# main.net
KiCad netlist of a schematic drawn in Altium Designer
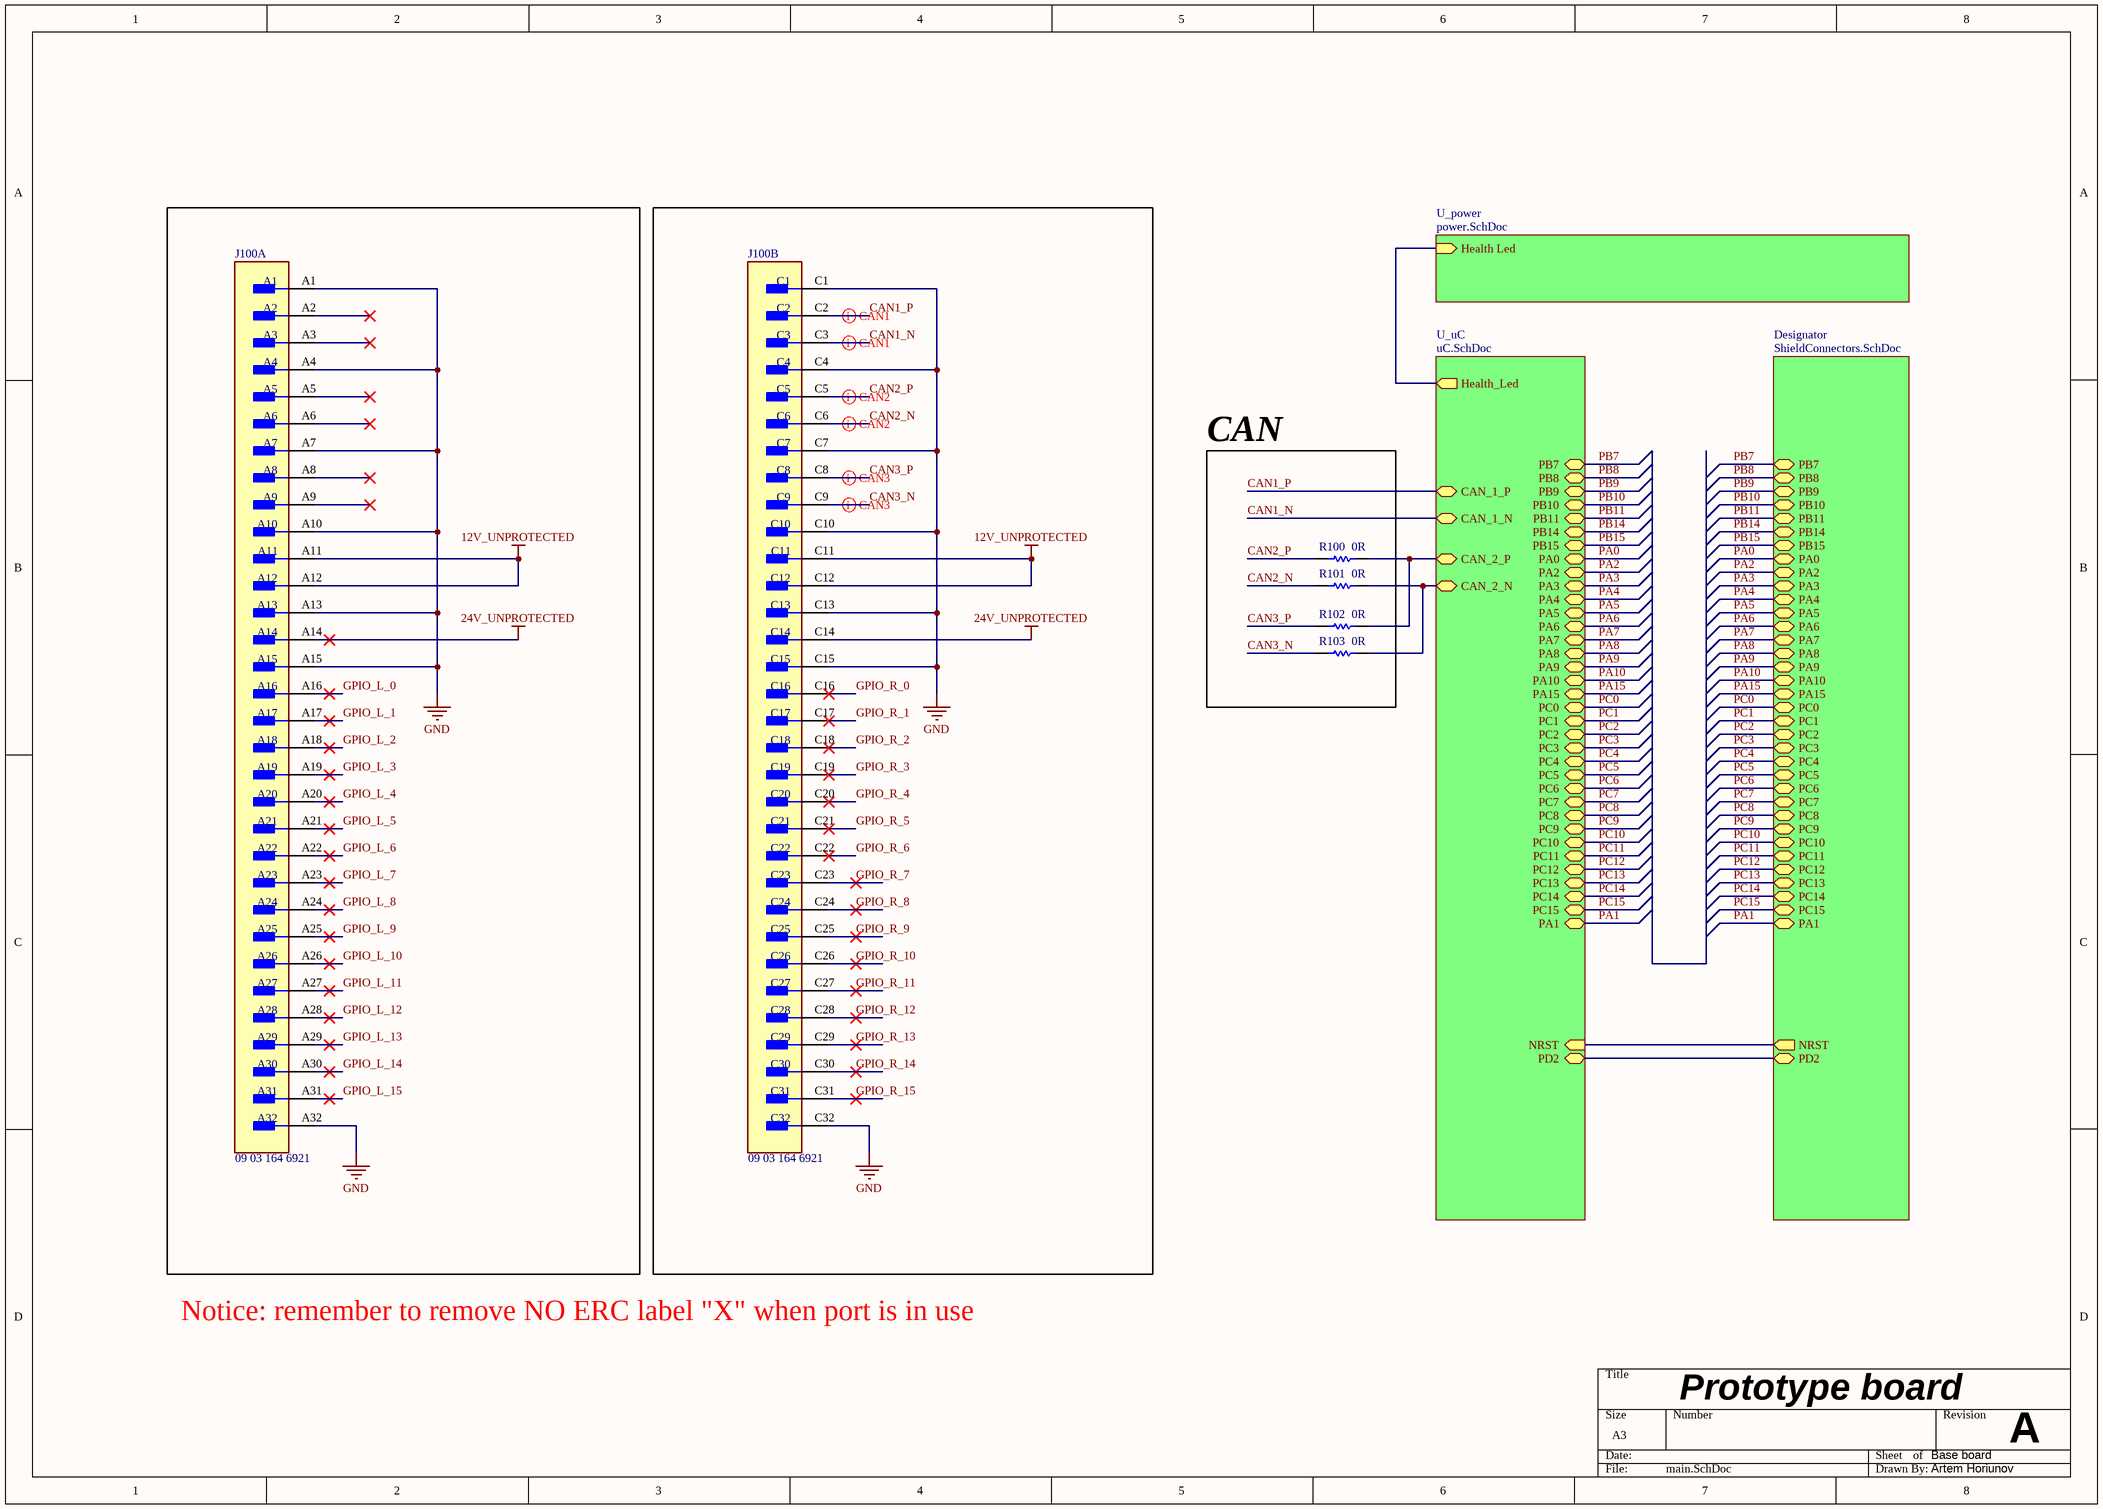
[diagram p0: main.SchDoc]

(export (version "E")
  (design (tool "Eeschema 10.0.6"))
  (components
    (comp (ref "J100")
      (value "09 03 164 6921")
      (footprint "FP-09_03_164_6921-MFG")
      (description "CONN DIN HDR 96POS PCB RA")
      (fields
        (field (name "MANUFACTURER") "Harting")
        (field (name "OCTOPART") "https://octopart.com/09031646921-harting+elektronik-42933")
      )
      (libsource (lib "Altium Content Vault") (part "242112e785ae82ea23b0e3c1eadb5b2"))
    )
    (comp (ref "R100")
      (value "0R")
      (footprint "RESC1608X55X25ML10T15")
      (description "Chip Resistor, 0 Ohm, +/- 5%, 0.1 W, -55 to 155 degC, 0603 (1608 Metric), RoHS, Tape and Reel")
      (fields (field (name "TOLERANCE") "5%") (field (name "MANUFACTURER") "Yageo"))
      (libsource (lib "Altium Content Vault") (part "RES-2"))
    )
    (comp (ref "R101")
      (value "0R")
      (footprint "RESC1608X55X25ML10T15")
      (description "Chip Resistor, 0 Ohm, +/- 5%, 0.1 W, -55 to 155 degC, 0603 (1608 Metric), RoHS, Tape and Reel")
      (fields (field (name "TOLERANCE") "5%") (field (name "MANUFACTURER") "Yageo"))
      (libsource (lib "Altium Content Vault") (part "RES-2"))
    )
    (comp (ref "R102")
      (value "0R")
      (footprint "RESC1608X55X25ML10T15")
      (description "Chip Resistor, 0 Ohm, +/- 5%, 0.1 W, -55 to 155 degC, 0603 (1608 Metric), RoHS, Tape and Reel")
      (fields (field (name "TOLERANCE") "5%") (field (name "MANUFACTURER") "Yageo"))
      (libsource (lib "Altium Content Vault") (part "RES-2"))
    )
    (comp (ref "R103")
      (value "0R")
      (footprint "RESC1608X55X25ML10T15")
      (description "Chip Resistor, 0 Ohm, +/- 5%, 0.1 W, -55 to 155 degC, 0603 (1608 Metric), RoHS, Tape and Reel")
      (fields (field (name "TOLERANCE") "5%") (field (name "MANUFACTURER") "Yageo"))
      (libsource (lib "Altium Content Vault") (part "RES-2"))
    )
  )
  (nets
    (net (code "1") (name "/CAN1_N") (class "Default")
      (node (ref "J100") (pin "C3") (pinfunction "C3_C3") (pintype "passive"))
    )
    (net (code "2") (name "/CAN1_P") (class "Default")
      (node (ref "J100") (pin "C2") (pinfunction "C2_C2") (pintype "passive"))
    )
    (net (code "3") (name "/CAN2_N") (class "Default")
      (node (ref "J100") (pin "C6") (pinfunction "C6_C6") (pintype "passive"))
      (node (ref "R101") (pin "1") (pinfunction "1_1") (pintype "passive"))
    )
    (net (code "4") (name "/CAN2_P") (class "Default")
      (node (ref "J100") (pin "C5") (pinfunction "C5_C5") (pintype "passive"))
      (node (ref "R100") (pin "1") (pinfunction "1_1") (pintype "passive"))
    )
    (net (code "5") (name "/CAN3_N") (class "Default")
      (node (ref "J100") (pin "C9") (pinfunction "C9_C9") (pintype "passive"))
      (node (ref "R103") (pin "1") (pinfunction "1_1") (pintype "passive"))
    )
    (net (code "6") (name "/CAN3_P") (class "Default")
      (node (ref "J100") (pin "C8") (pinfunction "C8_C8") (pintype "passive"))
      (node (ref "R102") (pin "1") (pinfunction "1_1") (pintype "passive"))
    )
    (net (code "7") (name "/CAN_2_N") (class "Default")
      (node (ref "R101") (pin "2") (pinfunction "2_2") (pintype "passive"))
      (node (ref "R103") (pin "2") (pinfunction "2_2") (pintype "passive"))
    )
    (net (code "8") (name "/CAN_2_P") (class "Default")
      (node (ref "R100") (pin "2") (pinfunction "2_2") (pintype "passive"))
      (node (ref "R102") (pin "2") (pinfunction "2_2") (pintype "passive"))
    )
    (net (code "9") (name "/GPIO_L_0") (class "Default")
      (node (ref "J100") (pin "A16") (pinfunction "A16_A16") (pintype "passive"))
    )
    (net (code "10") (name "/GPIO_L_1") (class "Default")
      (node (ref "J100") (pin "A17") (pinfunction "A17_A17") (pintype "passive"))
    )
    (net (code "11") (name "/GPIO_L_2") (class "Default")
      (node (ref "J100") (pin "A18") (pinfunction "A18_A18") (pintype "passive"))
    )
    (net (code "12") (name "/GPIO_L_3") (class "Default")
      (node (ref "J100") (pin "A19") (pinfunction "A19_A19") (pintype "passive"))
    )
    (net (code "13") (name "/GPIO_L_4") (class "Default")
      (node (ref "J100") (pin "A20") (pinfunction "A20_A20") (pintype "passive"))
    )
    (net (code "14") (name "/GPIO_L_5") (class "Default")
      (node (ref "J100") (pin "A21") (pinfunction "A21_A21") (pintype "passive"))
    )
    (net (code "15") (name "/GPIO_L_6") (class "Default")
      (node (ref "J100") (pin "A22") (pinfunction "A22_A22") (pintype "passive"))
    )
    (net (code "16") (name "/GPIO_L_7") (class "Default")
      (node (ref "J100") (pin "A23") (pinfunction "A23_A23") (pintype "passive"))
    )
    (net (code "17") (name "/GPIO_L_8") (class "Default")
      (node (ref "J100") (pin "A24") (pinfunction "A24_A24") (pintype "passive"))
    )
    (net (code "18") (name "/GPIO_L_9") (class "Default")
      (node (ref "J100") (pin "A25") (pinfunction "A25_A25") (pintype "passive"))
    )
    (net (code "19") (name "/GPIO_L_10") (class "Default")
      (node (ref "J100") (pin "A26") (pinfunction "A26_A26") (pintype "passive"))
    )
    (net (code "20") (name "/GPIO_L_11") (class "Default")
      (node (ref "J100") (pin "A27") (pinfunction "A27_A27") (pintype "passive"))
    )
    (net (code "21") (name "/GPIO_L_12") (class "Default")
      (node (ref "J100") (pin "A28") (pinfunction "A28_A28") (pintype "passive"))
    )
    (net (code "22") (name "/GPIO_L_13") (class "Default")
      (node (ref "J100") (pin "A29") (pinfunction "A29_A29") (pintype "passive"))
    )
    (net (code "23") (name "/GPIO_L_14") (class "Default")
      (node (ref "J100") (pin "A30") (pinfunction "A30_A30") (pintype "passive"))
    )
    (net (code "24") (name "/GPIO_L_15") (class "Default")
      (node (ref "J100") (pin "A31") (pinfunction "A31_A31") (pintype "passive"))
    )
    (net (code "25") (name "/GPIO_R_0") (class "Default")
      (node (ref "J100") (pin "C16") (pinfunction "C16_C16") (pintype "passive+no_connect"))
    )
    (net (code "26") (name "/GPIO_R_1") (class "Default")
      (node (ref "J100") (pin "C17") (pinfunction "C17_C17") (pintype "passive+no_connect"))
    )
    (net (code "27") (name "/GPIO_R_2") (class "Default")
      (node (ref "J100") (pin "C18") (pinfunction "C18_C18") (pintype "passive+no_connect"))
    )
    (net (code "28") (name "/GPIO_R_3") (class "Default")
      (node (ref "J100") (pin "C19") (pinfunction "C19_C19") (pintype "passive+no_connect"))
    )
    (net (code "29") (name "/GPIO_R_4") (class "Default")
      (node (ref "J100") (pin "C20") (pinfunction "C20_C20") (pintype "passive+no_connect"))
    )
    (net (code "30") (name "/GPIO_R_5") (class "Default")
      (node (ref "J100") (pin "C21") (pinfunction "C21_C21") (pintype "passive+no_connect"))
    )
    (net (code "31") (name "/GPIO_R_6") (class "Default")
      (node (ref "J100") (pin "C22") (pinfunction "C22_C22") (pintype "passive+no_connect"))
    )
    (net (code "79") (name "/GPIO_R_7") (class "Default")
      (node (ref "J100") (pin "C23") (pinfunction "C23_C23") (pintype "passive"))
    )
    (net (code "80") (name "/GPIO_R_8") (class "Default")
      (node (ref "J100") (pin "C24") (pinfunction "C24_C24") (pintype "passive"))
    )
    (net (code "81") (name "/GPIO_R_9") (class "Default")
      (node (ref "J100") (pin "C25") (pinfunction "C25_C25") (pintype "passive"))
    )
    (net (code "82") (name "/GPIO_R_10") (class "Default")
      (node (ref "J100") (pin "C26") (pinfunction "C26_C26") (pintype "passive"))
    )
    (net (code "83") (name "/GPIO_R_11") (class "Default")
      (node (ref "J100") (pin "C27") (pinfunction "C27_C27") (pintype "passive"))
    )
    (net (code "84") (name "/GPIO_R_12") (class "Default")
      (node (ref "J100") (pin "C28") (pinfunction "C28_C28") (pintype "passive"))
    )
    (net (code "85") (name "/GPIO_R_13") (class "Default")
      (node (ref "J100") (pin "C29") (pinfunction "C29_C29") (pintype "passive"))
    )
    (net (code "86") (name "/GPIO_R_14") (class "Default")
      (node (ref "J100") (pin "C30") (pinfunction "C30_C30") (pintype "passive"))
    )
    (net (code "87") (name "/GPIO_R_15") (class "Default")
      (node (ref "J100") (pin "C31") (pinfunction "C31_C31") (pintype "passive"))
    )
    (net (code "88") (name "12V_UNPROTECTED") (class "Default")
      (node (ref "J100") (pin "A11") (pinfunction "A11_A11") (pintype "passive"))
      (node (ref "J100") (pin "A12") (pinfunction "A12_A12") (pintype "passive"))
      (node (ref "J100") (pin "C11") (pinfunction "C11_C11") (pintype "passive"))
      (node (ref "J100") (pin "C12") (pinfunction "C12_C12") (pintype "passive"))
    )
    (net (code "89") (name "24V_UNPROTECTED") (class "Default")
      (node (ref "J100") (pin "A14") (pinfunction "A14_A14") (pintype "passive"))
      (node (ref "J100") (pin "C14") (pinfunction "C14_C14") (pintype "passive"))
    )
    (net (code "90") (name "GND") (class "Default")
      (node (ref "J100") (pin "A1") (pinfunction "A1_A1") (pintype "passive"))
      (node (ref "J100") (pin "A10") (pinfunction "A10_A10") (pintype "passive"))
      (node (ref "J100") (pin "A13") (pinfunction "A13_A13") (pintype "passive"))
      (node (ref "J100") (pin "A15") (pinfunction "A15_A15") (pintype "passive"))
      (node (ref "J100") (pin "A32") (pinfunction "A32_A32") (pintype "passive"))
      (node (ref "J100") (pin "A4") (pinfunction "A4_A4") (pintype "passive"))
      (node (ref "J100") (pin "A7") (pinfunction "A7_A7") (pintype "passive"))
      (node (ref "J100") (pin "C1") (pinfunction "C1_C1") (pintype "passive"))
      (node (ref "J100") (pin "C10") (pinfunction "C10_C10") (pintype "passive"))
      (node (ref "J100") (pin "C13") (pinfunction "C13_C13") (pintype "passive"))
      (node (ref "J100") (pin "C15") (pinfunction "C15_C15") (pintype "passive"))
      (node (ref "J100") (pin "C32") (pinfunction "C32_C32") (pintype "passive"))
      (node (ref "J100") (pin "C4") (pinfunction "C4_C4") (pintype "passive"))
      (node (ref "J100") (pin "C7") (pinfunction "C7_C7") (pintype "passive"))
    )
    (net (code "91") (name "unconnected-(J100-PadA2)") (class "Default")
      (node (ref "J100") (pin "A2") (pinfunction "A2_A2") (pintype "passive+no_connect"))
    )
    (net (code "92") (name "unconnected-(J100-PadA3)") (class "Default")
      (node (ref "J100") (pin "A3") (pinfunction "A3_A3") (pintype "passive+no_connect"))
    )
    (net (code "93") (name "unconnected-(J100-PadA5)") (class "Default")
      (node (ref "J100") (pin "A5") (pinfunction "A5_A5") (pintype "passive+no_connect"))
    )
    (net (code "94") (name "unconnected-(J100-PadA6)") (class "Default")
      (node (ref "J100") (pin "A6") (pinfunction "A6_A6") (pintype "passive+no_connect"))
    )
    (net (code "95") (name "unconnected-(J100-PadA8)") (class "Default")
      (node (ref "J100") (pin "A8") (pinfunction "A8_A8") (pintype "passive+no_connect"))
    )
    (net (code "96") (name "unconnected-(J100-PadA9)") (class "Default")
      (node (ref "J100") (pin "A9") (pinfunction "A9_A9") (pintype "passive+no_connect"))
    )
  )
)
